# sddrive.net
KiCad netlist of a schematic drawn in EAGLE
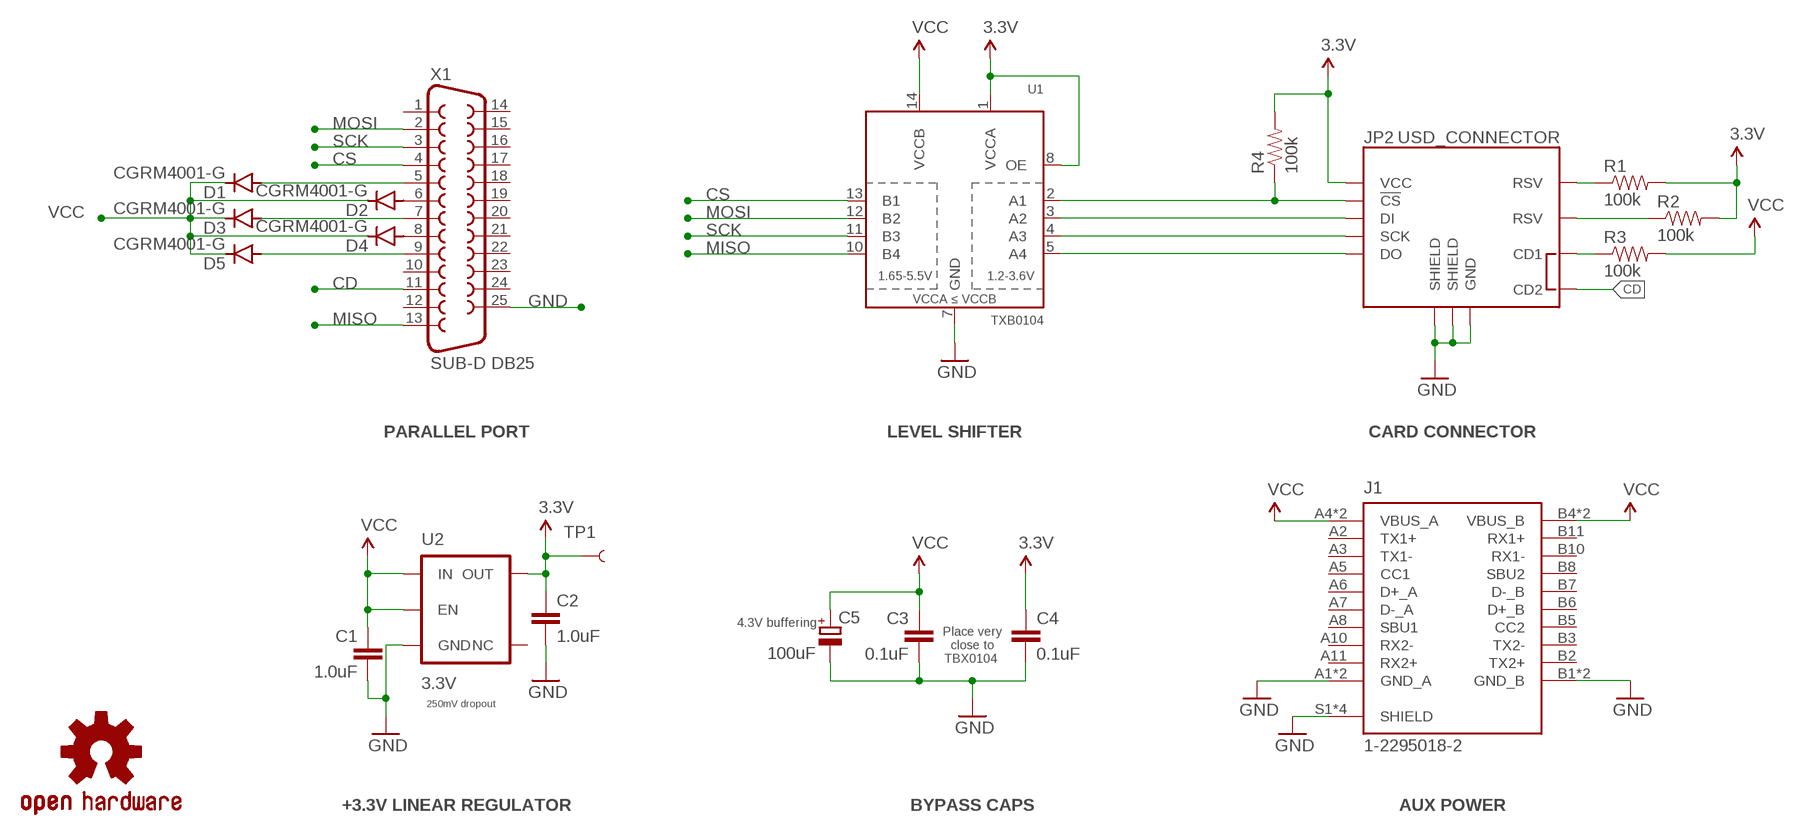
[diagram p0: schematic, sheet 1]

(export (version "E")
  (design (tool "Eeschema 10.0.6"))
  (components
    (comp (ref "C1")
      (value "1.0uF")
      (footprint "eagle-import:0603-CAP")
      (libsource (lib "eagle-import") (part "1.0UF-16V-10%(0603)"))
    )
    (comp (ref "C2")
      (value "1.0uF")
      (footprint "eagle-import:0603-CAP")
      (libsource (lib "eagle-import") (part "1.0UF-16V-10%(0603)"))
    )
    (comp (ref "C3")
      (value "0.1uF")
      (footprint "eagle-import:0603-CAP")
      (libsource (lib "eagle-import") (part "0.1UF-25V(+80/-20%)(0603)"))
    )
    (comp (ref "C4")
      (value "0.1uF")
      (footprint "eagle-import:0603-CAP")
      (libsource (lib "eagle-import") (part "0.1UF-25V(+80/-20%)(0603)"))
    )
    (comp (ref "C5")
      (value "100uF")
      (footprint "eagle-import:PANASONIC_C")
      (libsource (lib "eagle-import") (part "CPOL-EUC"))
    )
    (comp (ref "D1")
      (value "CGRM4001-G")
      (footprint "eagle-import:SOD-123_MINI-SMA")
      (libsource (lib "eagle-import") (part "CGRM400-G1"))
    )
    (comp (ref "D2")
      (value "CGRM4001-G")
      (footprint "eagle-import:SOD-123_MINI-SMA")
      (libsource (lib "eagle-import") (part "CGRM400-G1"))
    )
    (comp (ref "D3")
      (value "CGRM4001-G")
      (footprint "eagle-import:SOD-123_MINI-SMA")
      (libsource (lib "eagle-import") (part "CGRM400-G1"))
    )
    (comp (ref "D4")
      (value "CGRM4001-G")
      (footprint "eagle-import:SOD-123_MINI-SMA")
      (libsource (lib "eagle-import") (part "CGRM400-G1"))
    )
    (comp (ref "D5")
      (value "CGRM4001-G")
      (footprint "eagle-import:SOD-123_MINI-SMA")
      (libsource (lib "eagle-import") (part "CGRM400-G1"))
    )
    (comp (ref "J1")
      (value "1-2295018-2")
      (footprint "eagle-import:TE_1-2295018-2")
      (fields (field (name "MF") "TE Connectivity AMP Connectors"))
      (libsource (lib "eagle-import") (part "1-2295018-2"))
    )
    (comp (ref "JP2")
      (value "USD_CONNECTOR")
      (footprint "eagle-import:MICRO-SD-SOCKET-PP")
      (libsource (lib "eagle-import") (part "USD_CONNECTOR"))
    )
    (comp (ref "LOGO2")
      (value "OSHW-LOGOS")
      (footprint "eagle-import:OSHW-LOGO-S")
      (libsource (lib "eagle-import") (part "OSHW-LOGOS"))
    )
    (comp (ref "R1")
      (value "100k")
      (footprint "eagle-import:0603-RES")
      (libsource (lib "eagle-import") (part "100KOHM-1/10W-1%(0603)"))
    )
    (comp (ref "R2")
      (value "100k")
      (footprint "eagle-import:0603-RES")
      (libsource (lib "eagle-import") (part "100KOHM-1/10W-1%(0603)"))
    )
    (comp (ref "R3")
      (value "100k")
      (footprint "eagle-import:0603-RES")
      (libsource (lib "eagle-import") (part "100KOHM-1/10W-1%(0603)"))
    )
    (comp (ref "R4")
      (value "100k")
      (footprint "eagle-import:0603-RES")
      (libsource (lib "eagle-import") (part "100KOHM-1/10W-1%(0603)"))
    )
    (comp (ref "TP1")
      (value "TEST-POINT3")
      (footprint "eagle-import:PAD.03X.03")
      (libsource (lib "eagle-import") (part "TEST-POINT3"))
    )
    (comp (ref "U1")
      (value "TXB0104")
      (footprint "eagle-import:SO14")
      (libsource (lib "eagle-import") (part "TXB0104PWRSOIC14"))
    )
    (comp (ref "U2")
      (value "3.3V")
      (footprint "eagle-import:SOT23-5")
      (libsource (lib "eagle-import") (part "V_REG_AP2112K-3.3V"))
    )
    (comp (ref "X1")
      (value "SUB-D DB25")
      (footprint "eagle-import:F25D")
      (libsource (lib "eagle-import") (part "F25D"))
    )
  )
  (nets
    (net (code "1") (name "/CS") (class "Default")
      (node (ref "U1") (pin "13") (pinfunction "B1_13") (pintype "bidirectional"))
      (node (ref "X1") (pin "4") (pinfunction "4_4") (pintype "passive"))
    )
    (net (code "2") (name "/MISO") (class "Default")
      (node (ref "U1") (pin "10") (pinfunction "B4_10") (pintype "bidirectional"))
      (node (ref "X1") (pin "13") (pinfunction "13_13") (pintype "passive"))
    )
    (net (code "3") (name "/MOSI") (class "Default")
      (node (ref "U1") (pin "12") (pinfunction "B2_12") (pintype "bidirectional"))
      (node (ref "X1") (pin "2") (pinfunction "2_2") (pintype "passive"))
    )
    (net (code "4") (name "/SCK") (class "Default")
      (node (ref "U1") (pin "11") (pinfunction "B3_11") (pintype "bidirectional"))
      (node (ref "X1") (pin "3") (pinfunction "3_3") (pintype "passive"))
    )
    (net (code "5") (name "3.3V") (class "Default")
      (node (ref "C2") (pin "1") (pinfunction "1_1") (pintype "passive"))
      (node (ref "C4") (pin "1") (pinfunction "1_1") (pintype "passive"))
      (node (ref "JP2") (pin "VCC") (pinfunction "VCC_VCC") (pintype "bidirectional"))
      (node (ref "R1") (pin "2") (pinfunction "2_2") (pintype "passive"))
      (node (ref "R2") (pin "2") (pinfunction "2_2") (pintype "passive"))
      (node (ref "R4") (pin "2") (pinfunction "2_2") (pintype "passive"))
      (node (ref "TP1") (pin "P$1") (pinfunction "1_P$1") (pintype "bidirectional"))
      (node (ref "U1") (pin "1") (pinfunction "VCCA_1") (pintype "bidirectional"))
      (node (ref "U1") (pin "8") (pinfunction "OE_8") (pintype "bidirectional"))
      (node (ref "U2") (pin "5") (pinfunction "OUT_5") (pintype "passive"))
    )
    (net (code "6") (name "CD") (class "Default")
      (node (ref "JP2") (pin "CD2") (pinfunction "CD2_CD2") (pintype "bidirectional"))
      (node (ref "X1") (pin "11") (pinfunction "11_11") (pintype "passive"))
    )
    (net (code "7") (name "GND") (class "Default")
      (node (ref "C1") (pin "2") (pinfunction "2_2") (pintype "passive"))
      (node (ref "C2") (pin "2") (pinfunction "2_2") (pintype "passive"))
      (node (ref "C3") (pin "2") (pinfunction "2_2") (pintype "passive"))
      (node (ref "C4") (pin "2") (pinfunction "2_2") (pintype "passive"))
      (node (ref "C5") (pin "-") (pinfunction "-_-") (pintype "passive"))
      (node (ref "J1") (pin "A1") (pinfunction "GND_A_A1") (pintype "power_in"))
      (node (ref "J1") (pin "A12") (pinfunction "GND_A_A12") (pintype "power_in"))
      (node (ref "J1") (pin "B1") (pinfunction "GND_B_B1") (pintype "power_in"))
      (node (ref "J1") (pin "B12") (pinfunction "GND_B_B12") (pintype "power_in"))
      (node (ref "J1") (pin "S1") (pinfunction "SHIELD_S1") (pintype "passive"))
      (node (ref "J1") (pin "S2") (pinfunction "SHIELD_S2") (pintype "passive"))
      (node (ref "J1") (pin "S3") (pinfunction "SHIELD_S3") (pintype "passive"))
      (node (ref "J1") (pin "S4") (pinfunction "SHIELD_S4") (pintype "passive"))
      (node (ref "JP2") (pin "GND") (pinfunction "GND_GND") (pintype "bidirectional"))
      (node (ref "JP2") (pin "GND1") (pinfunction "SHIELD_GND1") (pintype "bidirectional"))
      (node (ref "JP2") (pin "GND3") (pinfunction "SHIELD_GND3") (pintype "bidirectional"))
      (node (ref "U1") (pin "7") (pinfunction "GND_7") (pintype "bidirectional"))
      (node (ref "U2") (pin "2") (pinfunction "GND_2") (pintype "input"))
      (node (ref "X1") (pin "25") (pinfunction "25_25") (pintype "passive"))
    )
    (net (code "8") (name "Net-(D1-PadA)") (class "Default")
      (node (ref "D1") (pin "A") (pinfunction "A_A") (pintype "passive"))
      (node (ref "X1") (pin "5") (pinfunction "5_5") (pintype "passive"))
    )
    (net (code "9") (name "Net-(D2-PadA)") (class "Default")
      (node (ref "D2") (pin "A") (pinfunction "A_A") (pintype "passive"))
      (node (ref "X1") (pin "6") (pinfunction "6_6") (pintype "passive"))
    )
    (net (code "10") (name "Net-(D3-PadA)") (class "Default")
      (node (ref "D3") (pin "A") (pinfunction "A_A") (pintype "passive"))
      (node (ref "X1") (pin "7") (pinfunction "7_7") (pintype "passive"))
    )
    (net (code "11") (name "Net-(D4-PadA)") (class "Default")
      (node (ref "D4") (pin "A") (pinfunction "A_A") (pintype "passive"))
      (node (ref "X1") (pin "8") (pinfunction "8_8") (pintype "passive"))
    )
    (net (code "12") (name "Net-(D5-PadA)") (class "Default")
      (node (ref "D5") (pin "A") (pinfunction "A_A") (pintype "passive"))
      (node (ref "X1") (pin "9") (pinfunction "9_9") (pintype "passive"))
    )
    (net (code "13") (name "Net-(JP2-PadCD1)") (class "Default")
      (node (ref "JP2") (pin "CD1") (pinfunction "CD1_CD1") (pintype "bidirectional"))
      (node (ref "R3") (pin "1") (pinfunction "1_1") (pintype "passive"))
    )
    (net (code "14") (name "Net-(JP2-RSV-PadRSV1)") (class "Default")
      (node (ref "JP2") (pin "RSV1") (pinfunction "RSV_RSV1") (pintype "bidirectional"))
      (node (ref "R1") (pin "1") (pinfunction "1_1") (pintype "passive"))
    )
    (net (code "15") (name "Net-(JP2-RSV-PadRSV2)") (class "Default")
      (node (ref "JP2") (pin "RSV2") (pinfunction "RSV_RSV2") (pintype "bidirectional"))
      (node (ref "R2") (pin "1") (pinfunction "1_1") (pintype "passive"))
    )
    (net (code "16") (name "Net-(JP2-SCK)") (class "Default")
      (node (ref "JP2") (pin "SCLK") (pinfunction "SCK_SCLK") (pintype "bidirectional"))
      (node (ref "U1") (pin "4") (pinfunction "A3_4") (pintype "bidirectional"))
    )
    (net (code "17") (name "Net-(JP2-~{CS})") (class "Default")
      (node (ref "JP2") (pin "CS") (pinfunction "~{CS}_CS") (pintype "bidirectional"))
      (node (ref "R4") (pin "1") (pinfunction "1_1") (pintype "passive"))
      (node (ref "U1") (pin "2") (pinfunction "A1_2") (pintype "bidirectional"))
    )
    (net (code "18") (name "Net-(U1-A2)") (class "Default")
      (node (ref "JP2") (pin "DI") (pinfunction "DI_DI") (pintype "bidirectional"))
      (node (ref "U1") (pin "3") (pinfunction "A2_3") (pintype "bidirectional"))
    )
    (net (code "19") (name "Net-(U1-A4)") (class "Default")
      (node (ref "JP2") (pin "DO") (pinfunction "DO_DO") (pintype "bidirectional"))
      (node (ref "U1") (pin "5") (pinfunction "A4_5") (pintype "bidirectional"))
    )
    (net (code "20") (name "VCC") (class "Default")
      (node (ref "C1") (pin "1") (pinfunction "1_1") (pintype "passive"))
      (node (ref "C3") (pin "1") (pinfunction "1_1") (pintype "passive"))
      (node (ref "C5") (pin "+") (pinfunction "+_+") (pintype "passive"))
      (node (ref "D1") (pin "C") (pinfunction "C_C") (pintype "passive"))
      (node (ref "D2") (pin "C") (pinfunction "C_C") (pintype "passive"))
      (node (ref "D3") (pin "C") (pinfunction "C_C") (pintype "passive"))
      (node (ref "D4") (pin "C") (pinfunction "C_C") (pintype "passive"))
      (node (ref "D5") (pin "C") (pinfunction "C_C") (pintype "passive"))
      (node (ref "J1") (pin "A4") (pinfunction "VBUS_A_A4") (pintype "power_in"))
      (node (ref "J1") (pin "A9") (pinfunction "VBUS_A_A9") (pintype "power_in"))
      (node (ref "J1") (pin "B4") (pinfunction "VBUS_B_B4") (pintype "power_in"))
      (node (ref "J1") (pin "B9") (pinfunction "VBUS_B_B9") (pintype "power_in"))
      (node (ref "R3") (pin "2") (pinfunction "2_2") (pintype "passive"))
      (node (ref "U1") (pin "14") (pinfunction "VCCB_14") (pintype "bidirectional"))
      (node (ref "U2") (pin "1") (pinfunction "IN_1") (pintype "input"))
      (node (ref "U2") (pin "3") (pinfunction "EN_3") (pintype "input"))
    )
    (net (code "21") (name "unconnected-(J1-CC1-PadA5)") (class "Default")
      (node (ref "J1") (pin "A5") (pinfunction "CC1_A5") (pintype "bidirectional"))
    )
    (net (code "22") (name "unconnected-(J1-CC2-PadB5)") (class "Default")
      (node (ref "J1") (pin "B5") (pinfunction "CC2_B5") (pintype "bidirectional"))
    )
    (net (code "23") (name "unconnected-(J1-D+_A-PadA6)") (class "Default")
      (node (ref "J1") (pin "A6") (pinfunction "D+_A_A6") (pintype "bidirectional"))
    )
    (net (code "24") (name "unconnected-(J1-D+_B-PadB6)") (class "Default")
      (node (ref "J1") (pin "B6") (pinfunction "D+_B_B6") (pintype "bidirectional"))
    )
    (net (code "25") (name "unconnected-(J1-D-_A-PadA7)") (class "Default")
      (node (ref "J1") (pin "A7") (pinfunction "D-_A_A7") (pintype "bidirectional"))
    )
    (net (code "26") (name "unconnected-(J1-D-_B-PadB7)") (class "Default")
      (node (ref "J1") (pin "B7") (pinfunction "D-_B_B7") (pintype "bidirectional"))
    )
    (net (code "27") (name "unconnected-(J1-RX1+-PadB11)") (class "Default")
      (node (ref "J1") (pin "B11") (pinfunction "RX1+_B11") (pintype "bidirectional"))
    )
    (net (code "28") (name "unconnected-(J1-RX1--PadB10)") (class "Default")
      (node (ref "J1") (pin "B10") (pinfunction "RX1-_B10") (pintype "bidirectional"))
    )
    (net (code "29") (name "unconnected-(J1-RX2+-PadA11)") (class "Default")
      (node (ref "J1") (pin "A11") (pinfunction "RX2+_A11") (pintype "bidirectional"))
    )
    (net (code "30") (name "unconnected-(J1-RX2--PadA10)") (class "Default")
      (node (ref "J1") (pin "A10") (pinfunction "RX2-_A10") (pintype "bidirectional"))
    )
    (net (code "31") (name "unconnected-(J1-SBU1-PadA8)") (class "Default")
      (node (ref "J1") (pin "A8") (pinfunction "SBU1_A8") (pintype "bidirectional"))
    )
    (net (code "32") (name "unconnected-(J1-SBU2-PadB8)") (class "Default")
      (node (ref "J1") (pin "B8") (pinfunction "SBU2_B8") (pintype "bidirectional"))
    )
    (net (code "33") (name "unconnected-(J1-TX1+-PadA2)") (class "Default")
      (node (ref "J1") (pin "A2") (pinfunction "TX1+_A2") (pintype "bidirectional"))
    )
    (net (code "34") (name "unconnected-(J1-TX1--PadA3)") (class "Default")
      (node (ref "J1") (pin "A3") (pinfunction "TX1-_A3") (pintype "bidirectional"))
    )
    (net (code "35") (name "unconnected-(J1-TX2+-PadB2)") (class "Default")
      (node (ref "J1") (pin "B2") (pinfunction "TX2+_B2") (pintype "bidirectional"))
    )
    (net (code "36") (name "unconnected-(J1-TX2--PadB3)") (class "Default")
      (node (ref "J1") (pin "B3") (pinfunction "TX2-_B3") (pintype "bidirectional"))
    )
    (net (code "37") (name "unconnected-(U2-NC-Pad4)") (class "Default")
      (node (ref "U2") (pin "4") (pinfunction "NC_4") (pintype "input"))
    )
    (net (code "38") (name "unconnected-(X1-Pad1)") (class "Default")
      (node (ref "X1") (pin "1") (pinfunction "1_1") (pintype "passive"))
    )
    (net (code "39") (name "unconnected-(X1-Pad10)") (class "Default")
      (node (ref "X1") (pin "10") (pinfunction "10_10") (pintype "passive"))
    )
    (net (code "40") (name "unconnected-(X1-Pad12)") (class "Default")
      (node (ref "X1") (pin "12") (pinfunction "12_12") (pintype "passive"))
    )
    (net (code "41") (name "unconnected-(X1-Pad14)") (class "Default")
      (node (ref "X1") (pin "14") (pinfunction "14_14") (pintype "passive"))
    )
    (net (code "42") (name "unconnected-(X1-Pad15)") (class "Default")
      (node (ref "X1") (pin "15") (pinfunction "15_15") (pintype "passive"))
    )
    (net (code "43") (name "unconnected-(X1-Pad16)") (class "Default")
      (node (ref "X1") (pin "16") (pinfunction "16_16") (pintype "passive"))
    )
    (net (code "44") (name "unconnected-(X1-Pad17)") (class "Default")
      (node (ref "X1") (pin "17") (pinfunction "17_17") (pintype "passive"))
    )
    (net (code "45") (name "unconnected-(X1-Pad18)") (class "Default")
      (node (ref "X1") (pin "18") (pinfunction "18_18") (pintype "passive"))
    )
    (net (code "46") (name "unconnected-(X1-Pad19)") (class "Default")
      (node (ref "X1") (pin "19") (pinfunction "19_19") (pintype "passive"))
    )
    (net (code "47") (name "unconnected-(X1-Pad20)") (class "Default")
      (node (ref "X1") (pin "20") (pinfunction "20_20") (pintype "passive"))
    )
    (net (code "48") (name "unconnected-(X1-Pad21)") (class "Default")
      (node (ref "X1") (pin "21") (pinfunction "21_21") (pintype "passive"))
    )
    (net (code "49") (name "unconnected-(X1-Pad22)") (class "Default")
      (node (ref "X1") (pin "22") (pinfunction "22_22") (pintype "passive"))
    )
    (net (code "50") (name "unconnected-(X1-Pad23)") (class "Default")
      (node (ref "X1") (pin "23") (pinfunction "23_23") (pintype "passive"))
    )
    (net (code "51") (name "unconnected-(X1-Pad24)") (class "Default")
      (node (ref "X1") (pin "24") (pinfunction "24_24") (pintype "passive"))
    )
  )
)
